# RelayController.net
KiCad netlist of a schematic drawn in EAGLE
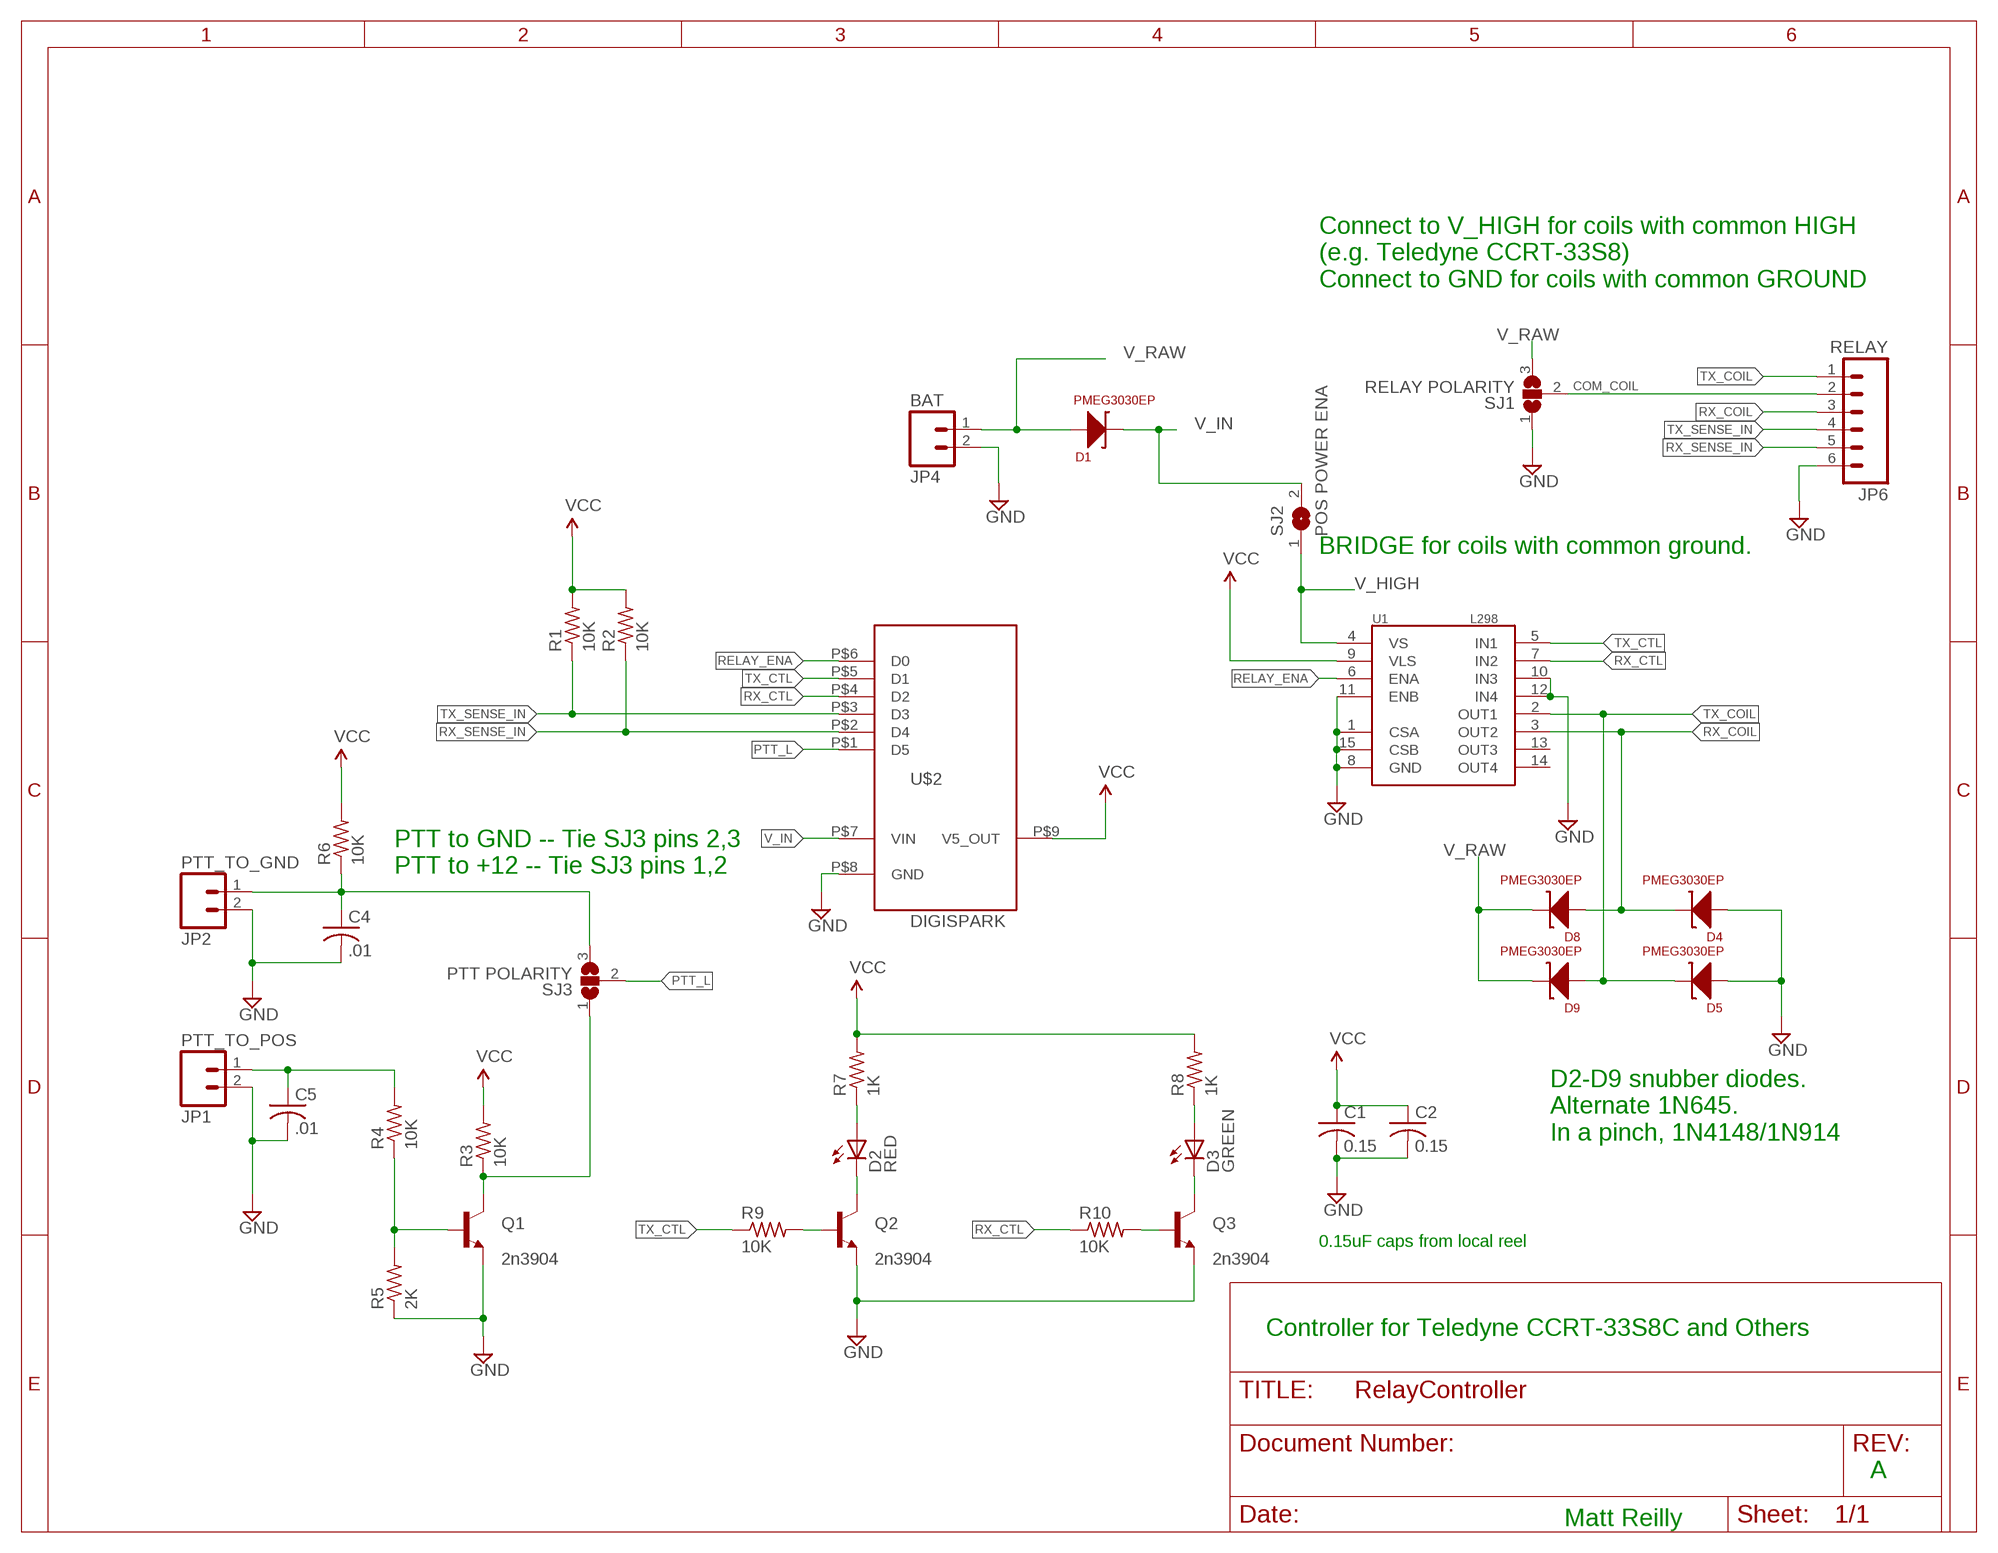
[diagram p0: schematic, sheet 1]

(export (version "E")
  (design (tool "Eeschema 10.0.6"))
  (components
    (comp (ref "C1")
      (value "0.15")
      (footprint "eagle-import:C1206K")
      (libsource (lib "eagle-import") (part "C-USC1206K"))
    )
    (comp (ref "C2")
      (value "0.15")
      (footprint "eagle-import:C1206K")
      (libsource (lib "eagle-import") (part "C-USC1206K"))
    )
    (comp (ref "C4")
      (value ".01")
      (footprint "eagle-import:C1206K")
      (libsource (lib "eagle-import") (part "C-USC1206K"))
    )
    (comp (ref "C5")
      (value ".01")
      (footprint "eagle-import:C1206K")
      (libsource (lib "eagle-import") (part "C-USC1206K"))
    )
    (comp (ref "D1")
      (value "PMEG3030EP")
      (footprint "eagle-import:SOD128")
      (libsource (lib "eagle-import") (part "PMEG3030EP"))
    )
    (comp (ref "D2")
      (value "RED")
      (footprint "eagle-import:LED3MM")
      (libsource (lib "eagle-import") (part "LED3MM"))
    )
    (comp (ref "D3")
      (value "GREEN")
      (footprint "eagle-import:LED3MM")
      (libsource (lib "eagle-import") (part "LED3MM"))
    )
    (comp (ref "D4")
      (value "PMEG3030EP")
      (footprint "eagle-import:SOD128")
      (libsource (lib "eagle-import") (part "PMEG3030EP"))
    )
    (comp (ref "D5")
      (value "PMEG3030EP")
      (footprint "eagle-import:SOD128")
      (libsource (lib "eagle-import") (part "PMEG3030EP"))
    )
    (comp (ref "D8")
      (value "PMEG3030EP")
      (footprint "eagle-import:SOD128")
      (libsource (lib "eagle-import") (part "PMEG3030EP"))
    )
    (comp (ref "D9")
      (value "PMEG3030EP")
      (footprint "eagle-import:SOD128")
      (libsource (lib "eagle-import") (part "PMEG3030EP"))
    )
    (comp (ref "JP1")
      (value "PTT_TO_POS")
      (footprint "eagle-import:SCREWTERMINAL-5MM-2")
      (libsource (lib "eagle-import") (part "M025MM"))
    )
    (comp (ref "JP2")
      (value "PTT_TO_GND")
      (footprint "eagle-import:SCREWTERMINAL-5MM-2")
      (libsource (lib "eagle-import") (part "M025MM"))
    )
    (comp (ref "JP4")
      (value "BAT")
      (footprint "eagle-import:SCREWTERMINAL-5MM-2")
      (libsource (lib "eagle-import") (part "M025MM"))
    )
    (comp (ref "JP6")
      (value "RELAY")
      (footprint "eagle-import:MOLEX-1X6")
      (libsource (lib "eagle-import") (part "M06POLAR"))
    )
    (comp (ref "Q1")
      (value "2n3904")
      (footprint "eagle-import:TO92")
      (libsource (lib "eagle-import") (part "2N3904"))
    )
    (comp (ref "Q2")
      (value "2n3904")
      (footprint "eagle-import:TO92")
      (libsource (lib "eagle-import") (part "2N3904"))
    )
    (comp (ref "Q3")
      (value "2n3904")
      (footprint "eagle-import:TO92")
      (libsource (lib "eagle-import") (part "2N3904"))
    )
    (comp (ref "R1")
      (value "10K")
      (footprint "eagle-import:R1206")
      (libsource (lib "eagle-import") (part "R-US_R1206"))
    )
    (comp (ref "R2")
      (value "10K")
      (footprint "eagle-import:R1206")
      (libsource (lib "eagle-import") (part "R-US_R1206"))
    )
    (comp (ref "R3")
      (value "10K")
      (footprint "eagle-import:R1206")
      (libsource (lib "eagle-import") (part "R-US_R1206"))
    )
    (comp (ref "R4")
      (value "10K")
      (footprint "eagle-import:R1206")
      (libsource (lib "eagle-import") (part "R-US_R1206"))
    )
    (comp (ref "R5")
      (value "2K")
      (footprint "eagle-import:R1206")
      (libsource (lib "eagle-import") (part "R-US_R1206"))
    )
    (comp (ref "R6")
      (value "10K")
      (footprint "eagle-import:R1206")
      (libsource (lib "eagle-import") (part "R-US_R1206"))
    )
    (comp (ref "R7")
      (value "1K")
      (footprint "eagle-import:R1206")
      (libsource (lib "eagle-import") (part "R-US_R1206"))
    )
    (comp (ref "R8")
      (value "1K")
      (footprint "eagle-import:R1206")
      (libsource (lib "eagle-import") (part "R-US_R1206"))
    )
    (comp (ref "R9")
      (value "10K")
      (footprint "eagle-import:R1206")
      (libsource (lib "eagle-import") (part "R-US_R1206"))
    )
    (comp (ref "R10")
      (value "10K")
      (footprint "eagle-import:R1206")
      (libsource (lib "eagle-import") (part "R-US_R1206"))
    )
    (comp (ref "SJ1")
      (value "RELAY POLARITY")
      (footprint "eagle-import:SJ_2W")
      (libsource (lib "eagle-import") (part "SJ2WW"))
    )
    (comp (ref "SJ2")
      (value "POS POWER ENA")
      (footprint "eagle-import:SJW")
      (libsource (lib "eagle-import") (part "SJW"))
    )
    (comp (ref "SJ3")
      (value "PTT POLARITY")
      (footprint "eagle-import:SJ_2W")
      (libsource (lib "eagle-import") (part "SJ2WW"))
    )
    (comp (ref "U$2")
      (value "DIGISPARK")
      (footprint "eagle-import:DIGISPARK_FP")
      (libsource (lib "eagle-import") (part "DIGISPARK"))
    )
    (comp (ref "U1")
      (value "L298")
      (footprint "eagle-import:MULTIWATT15")
      (libsource (lib "eagle-import") (part "L298"))
    )
  )
  (nets
    (net (code "1") (name "/COM_COIL") (class "Default")
      (node (ref "JP6") (pin "2") (pinfunction "2_2") (pintype "passive"))
      (node (ref "SJ1") (pin "2") (pinfunction "2_2") (pintype "passive"))
    )
    (net (code "2") (name "/V_HIGH") (class "Default")
      (node (ref "SJ2") (pin "1") (pinfunction "1_1") (pintype "passive"))
      (node (ref "U1") (pin "4") (pinfunction "VS_4") (pintype "bidirectional"))
    )
    (net (code "3") (name "/V_RAW") (class "Default")
      (node (ref "D1") (pin "P$1") (pinfunction "A_P$1") (pintype "bidirectional"))
      (node (ref "D8") (pin "P$2") (pinfunction "C_P$2") (pintype "bidirectional"))
      (node (ref "D9") (pin "P$2") (pinfunction "C_P$2") (pintype "bidirectional"))
      (node (ref "JP4") (pin "1") (pinfunction "1_1") (pintype "passive"))
      (node (ref "SJ1") (pin "3") (pinfunction "3_3") (pintype "passive"))
    )
    (net (code "4") (name "GND") (class "Default")
      (node (ref "C1") (pin "2") (pinfunction "2_2") (pintype "passive"))
      (node (ref "C2") (pin "2") (pinfunction "2_2") (pintype "passive"))
      (node (ref "C4") (pin "2") (pinfunction "2_2") (pintype "passive"))
      (node (ref "C5") (pin "2") (pinfunction "2_2") (pintype "passive"))
      (node (ref "D4") (pin "P$1") (pinfunction "A_P$1") (pintype "bidirectional"))
      (node (ref "D5") (pin "P$1") (pinfunction "A_P$1") (pintype "bidirectional"))
      (node (ref "JP1") (pin "2") (pinfunction "2_2") (pintype "passive"))
      (node (ref "JP2") (pin "2") (pinfunction "2_2") (pintype "passive"))
      (node (ref "JP4") (pin "2") (pinfunction "2_2") (pintype "passive"))
      (node (ref "JP6") (pin "6") (pinfunction "6_6") (pintype "passive"))
      (node (ref "Q1") (pin "3") (pinfunction "E_3") (pintype "passive"))
      (node (ref "Q2") (pin "3") (pinfunction "E_3") (pintype "passive"))
      (node (ref "Q3") (pin "3") (pinfunction "E_3") (pintype "passive"))
      (node (ref "R5") (pin "1") (pinfunction "1_1") (pintype "passive"))
      (node (ref "SJ1") (pin "1") (pinfunction "1_1") (pintype "passive"))
      (node (ref "U$2") (pin "P$8") (pinfunction "GND_P$8") (pintype "bidirectional"))
      (node (ref "U1") (pin "1") (pinfunction "CSA_1") (pintype "bidirectional"))
      (node (ref "U1") (pin "10") (pinfunction "IN3_10") (pintype "bidirectional"))
      (node (ref "U1") (pin "11") (pinfunction "ENB_11") (pintype "bidirectional"))
      (node (ref "U1") (pin "12") (pinfunction "IN4_12") (pintype "bidirectional"))
      (node (ref "U1") (pin "15") (pinfunction "CSB_15") (pintype "bidirectional"))
      (node (ref "U1") (pin "8") (pinfunction "GND_8") (pintype "bidirectional"))
    )
    (net (code "5") (name "Net-(C4-Pad1)") (class "Default")
      (node (ref "C4") (pin "1") (pinfunction "1_1") (pintype "passive"))
      (node (ref "JP2") (pin "1") (pinfunction "1_1") (pintype "passive"))
      (node (ref "R6") (pin "1") (pinfunction "1_1") (pintype "passive"))
      (node (ref "SJ3") (pin "3") (pinfunction "3_3") (pintype "passive"))
    )
    (net (code "6") (name "Net-(C5-Pad1)") (class "Default")
      (node (ref "C5") (pin "1") (pinfunction "1_1") (pintype "passive"))
      (node (ref "JP1") (pin "1") (pinfunction "1_1") (pintype "passive"))
      (node (ref "R4") (pin "2") (pinfunction "2_2") (pintype "passive"))
    )
    (net (code "7") (name "Net-(D2-C)") (class "Default")
      (node (ref "D2") (pin "K") (pinfunction "C_K") (pintype "passive"))
      (node (ref "Q2") (pin "1") (pinfunction "C_1") (pintype "passive"))
    )
    (net (code "8") (name "Net-(D2-PadA)") (class "Default")
      (node (ref "D2") (pin "A") (pinfunction "A_A") (pintype "passive"))
      (node (ref "R7") (pin "1") (pinfunction "1_1") (pintype "passive"))
    )
    (net (code "9") (name "Net-(D3-C)") (class "Default")
      (node (ref "D3") (pin "K") (pinfunction "C_K") (pintype "passive"))
      (node (ref "Q3") (pin "1") (pinfunction "C_1") (pintype "passive"))
    )
    (net (code "10") (name "Net-(D3-PadA)") (class "Default")
      (node (ref "D3") (pin "A") (pinfunction "A_A") (pintype "passive"))
      (node (ref "R8") (pin "1") (pinfunction "1_1") (pintype "passive"))
    )
    (net (code "11") (name "Net-(Q1-B)") (class "Default")
      (node (ref "Q1") (pin "2") (pinfunction "B_2") (pintype "passive"))
      (node (ref "R4") (pin "1") (pinfunction "1_1") (pintype "passive"))
      (node (ref "R5") (pin "2") (pinfunction "2_2") (pintype "passive"))
    )
    (net (code "12") (name "Net-(Q1-C)") (class "Default")
      (node (ref "Q1") (pin "1") (pinfunction "C_1") (pintype "passive"))
      (node (ref "R3") (pin "1") (pinfunction "1_1") (pintype "passive"))
      (node (ref "SJ3") (pin "1") (pinfunction "1_1") (pintype "passive"))
    )
    (net (code "13") (name "Net-(Q2-B)") (class "Default")
      (node (ref "Q2") (pin "2") (pinfunction "B_2") (pintype "passive"))
      (node (ref "R9") (pin "2") (pinfunction "2_2") (pintype "passive"))
    )
    (net (code "14") (name "Net-(Q3-B)") (class "Default")
      (node (ref "Q3") (pin "2") (pinfunction "B_2") (pintype "passive"))
      (node (ref "R10") (pin "2") (pinfunction "2_2") (pintype "passive"))
    )
    (net (code "15") (name "PTT_L") (class "Default")
      (node (ref "SJ3") (pin "2") (pinfunction "2_2") (pintype "passive"))
      (node (ref "U$2") (pin "P$1") (pinfunction "D5_P$1") (pintype "bidirectional"))
    )
    (net (code "16") (name "RELAY_ENA") (class "Default")
      (node (ref "U$2") (pin "P$6") (pinfunction "D0_P$6") (pintype "bidirectional"))
      (node (ref "U1") (pin "6") (pinfunction "ENA_6") (pintype "bidirectional"))
    )
    (net (code "17") (name "RX_COIL") (class "Default")
      (node (ref "D4") (pin "P$2") (pinfunction "C_P$2") (pintype "bidirectional"))
      (node (ref "D8") (pin "P$1") (pinfunction "A_P$1") (pintype "bidirectional"))
      (node (ref "JP6") (pin "3") (pinfunction "3_3") (pintype "passive"))
      (node (ref "U1") (pin "3") (pinfunction "OUT2_3") (pintype "bidirectional"))
    )
    (net (code "18") (name "RX_CTL") (class "Default")
      (node (ref "R10") (pin "1") (pinfunction "1_1") (pintype "passive"))
      (node (ref "U$2") (pin "P$4") (pinfunction "D2_P$4") (pintype "bidirectional"))
      (node (ref "U1") (pin "7") (pinfunction "IN2_7") (pintype "bidirectional"))
    )
    (net (code "19") (name "RX_SENSE_IN") (class "Default")
      (node (ref "JP6") (pin "5") (pinfunction "5_5") (pintype "passive"))
      (node (ref "R2") (pin "1") (pinfunction "1_1") (pintype "passive"))
      (node (ref "U$2") (pin "P$2") (pinfunction "D4_P$2") (pintype "bidirectional"))
    )
    (net (code "20") (name "TX_COIL") (class "Default")
      (node (ref "D5") (pin "P$2") (pinfunction "C_P$2") (pintype "bidirectional"))
      (node (ref "D9") (pin "P$1") (pinfunction "A_P$1") (pintype "bidirectional"))
      (node (ref "JP6") (pin "1") (pinfunction "1_1") (pintype "passive"))
      (node (ref "U1") (pin "2") (pinfunction "OUT1_2") (pintype "bidirectional"))
    )
    (net (code "21") (name "TX_CTL") (class "Default")
      (node (ref "R9") (pin "1") (pinfunction "1_1") (pintype "passive"))
      (node (ref "U$2") (pin "P$5") (pinfunction "D1_P$5") (pintype "bidirectional"))
      (node (ref "U1") (pin "5") (pinfunction "IN1_5") (pintype "bidirectional"))
    )
    (net (code "22") (name "TX_SENSE_IN") (class "Default")
      (node (ref "JP6") (pin "4") (pinfunction "4_4") (pintype "passive"))
      (node (ref "R1") (pin "1") (pinfunction "1_1") (pintype "passive"))
      (node (ref "U$2") (pin "P$3") (pinfunction "D3_P$3") (pintype "bidirectional"))
    )
    (net (code "23") (name "VCC") (class "Default")
      (node (ref "C1") (pin "1") (pinfunction "1_1") (pintype "passive"))
      (node (ref "C2") (pin "1") (pinfunction "1_1") (pintype "passive"))
      (node (ref "R1") (pin "2") (pinfunction "2_2") (pintype "passive"))
      (node (ref "R2") (pin "2") (pinfunction "2_2") (pintype "passive"))
      (node (ref "R3") (pin "2") (pinfunction "2_2") (pintype "passive"))
      (node (ref "R6") (pin "2") (pinfunction "2_2") (pintype "passive"))
      (node (ref "R7") (pin "2") (pinfunction "2_2") (pintype "passive"))
      (node (ref "R8") (pin "2") (pinfunction "2_2") (pintype "passive"))
      (node (ref "U$2") (pin "P$9") (pinfunction "V5_OUT_P$9") (pintype "bidirectional"))
      (node (ref "U1") (pin "9") (pinfunction "VLS_9") (pintype "bidirectional"))
    )
    (net (code "24") (name "V_IN") (class "Default")
      (node (ref "D1") (pin "P$2") (pinfunction "C_P$2") (pintype "bidirectional"))
      (node (ref "SJ2") (pin "2") (pinfunction "2_2") (pintype "passive"))
      (node (ref "U$2") (pin "P$7") (pinfunction "VIN_P$7") (pintype "bidirectional"))
    )
    (net (code "25") (name "unconnected-(U1-OUT3-Pad13)") (class "Default")
      (node (ref "U1") (pin "13") (pinfunction "OUT3_13") (pintype "bidirectional"))
    )
    (net (code "26") (name "unconnected-(U1-OUT4-Pad14)") (class "Default")
      (node (ref "U1") (pin "14") (pinfunction "OUT4_14") (pintype "bidirectional"))
    )
  )
)
